# watch.net
KiCad netlist of a schematic drawn in EAGLE
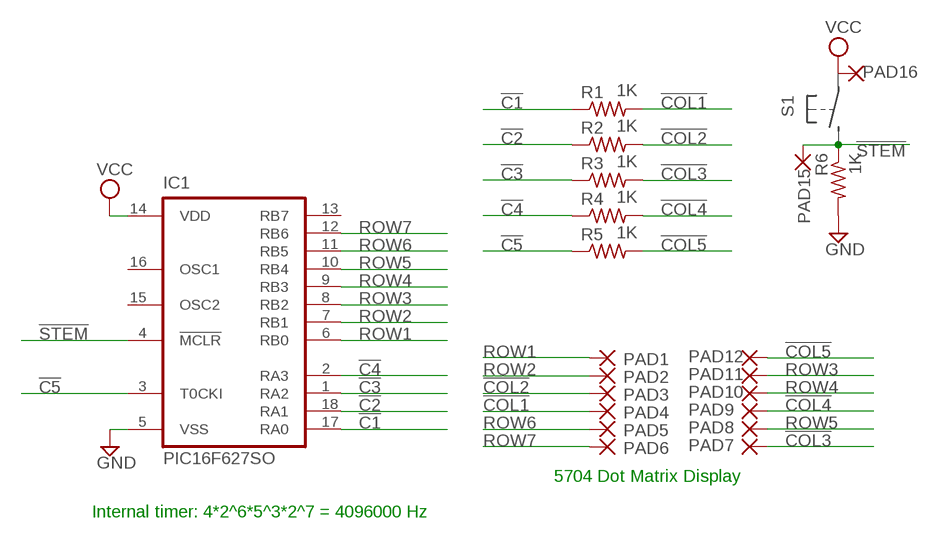
[diagram p0: schematic, sheet 1]

(export (version "E")
  (design (tool "Eeschema 10.0.6"))
  (components
    (comp (ref "IC1")
      (value "PIC16F627SO")
      (footprint "eagle-import:SO-18W")
      (fields (field (name "MF") "MICROCHIP") (field (name "MPN") "PIC16C622A-04I/SO"))
      (libsource (lib "eagle-import") (part "PIC16CSO622"))
    )
    (comp (ref "PAD1")
      (value "SMD2")
      (footprint "eagle-import:SMD1,27-2,54")
      (libsource (lib "eagle-import") (part "SMD2"))
    )
    (comp (ref "PAD2")
      (value "SMD2")
      (footprint "eagle-import:SMD1,27-2,54")
      (libsource (lib "eagle-import") (part "SMD2"))
    )
    (comp (ref "PAD3")
      (value "SMD2")
      (footprint "eagle-import:SMD1,27-2,54")
      (libsource (lib "eagle-import") (part "SMD2"))
    )
    (comp (ref "PAD4")
      (value "SMD2")
      (footprint "eagle-import:SMD1,27-2,54")
      (libsource (lib "eagle-import") (part "SMD2"))
    )
    (comp (ref "PAD5")
      (value "SMD2")
      (footprint "eagle-import:SMD1,27-2,54")
      (libsource (lib "eagle-import") (part "SMD2"))
    )
    (comp (ref "PAD6")
      (value "SMD2")
      (footprint "eagle-import:SMD1,27-2,54")
      (libsource (lib "eagle-import") (part "SMD2"))
    )
    (comp (ref "PAD7")
      (value "SMD2")
      (footprint "eagle-import:SMD1,27-2,54")
      (libsource (lib "eagle-import") (part "SMD2"))
    )
    (comp (ref "PAD8")
      (value "SMD2")
      (footprint "eagle-import:SMD1,27-2,54")
      (libsource (lib "eagle-import") (part "SMD2"))
    )
    (comp (ref "PAD9")
      (value "SMD2")
      (footprint "eagle-import:SMD1,27-2,54")
      (libsource (lib "eagle-import") (part "SMD2"))
    )
    (comp (ref "PAD10")
      (value "SMD2")
      (footprint "eagle-import:SMD1,27-2,54")
      (libsource (lib "eagle-import") (part "SMD2"))
    )
    (comp (ref "PAD11")
      (value "SMD2")
      (footprint "eagle-import:SMD1,27-2,54")
      (libsource (lib "eagle-import") (part "SMD2"))
    )
    (comp (ref "PAD12")
      (value "SMD2")
      (footprint "eagle-import:SMD1,27-2,54")
      (libsource (lib "eagle-import") (part "SMD2"))
    )
    (comp (ref "PAD15")
      (value "SMD2")
      (footprint "eagle-import:SMD1,27-2,54")
      (libsource (lib "eagle-import") (part "SMD2"))
    )
    (comp (ref "PAD16")
      (value "SMD2")
      (footprint "eagle-import:SMD1,27-2,54")
      (libsource (lib "eagle-import") (part "SMD2"))
    )
    (comp (ref "R1")
      (value "1K")
      (footprint "eagle-import:R0805")
      (libsource (lib "eagle-import") (part "R-US_R0805"))
    )
    (comp (ref "R2")
      (value "1K")
      (footprint "eagle-import:R0805")
      (libsource (lib "eagle-import") (part "R-US_R0805"))
    )
    (comp (ref "R3")
      (value "1K")
      (footprint "eagle-import:R0805")
      (libsource (lib "eagle-import") (part "R-US_R0805"))
    )
    (comp (ref "R4")
      (value "1K")
      (footprint "eagle-import:R0805")
      (libsource (lib "eagle-import") (part "R-US_R0805"))
    )
    (comp (ref "R5")
      (value "1K")
      (footprint "eagle-import:R0805")
      (libsource (lib "eagle-import") (part "R-US_R0805"))
    )
    (comp (ref "R6")
      (value "1K")
      (footprint "eagle-import:R0805")
      (libsource (lib "eagle-import") (part "R-US_R0805"))
    )
  )
  (nets
    (net (code "1") (name "/ROW1") (class "Default")
      (node (ref "IC1") (pin "6") (pinfunction "RB0_6") (pintype "bidirectional"))
      (node (ref "PAD1") (pin "1") (pinfunction "P_1") (pintype "passive"))
    )
    (net (code "2") (name "/ROW2") (class "Default")
      (node (ref "IC1") (pin "7") (pinfunction "RB1_7") (pintype "bidirectional"))
      (node (ref "PAD2") (pin "1") (pinfunction "P_1") (pintype "passive"))
    )
    (net (code "3") (name "/ROW3") (class "Default")
      (node (ref "IC1") (pin "8") (pinfunction "RB2_8") (pintype "bidirectional"))
      (node (ref "PAD11") (pin "1") (pinfunction "P_1") (pintype "passive"))
    )
    (net (code "4") (name "/ROW4") (class "Default")
      (node (ref "IC1") (pin "9") (pinfunction "RB3_9") (pintype "bidirectional"))
      (node (ref "PAD10") (pin "1") (pinfunction "P_1") (pintype "passive"))
    )
    (net (code "5") (name "/ROW5") (class "Default")
      (node (ref "IC1") (pin "10") (pinfunction "RB4_10") (pintype "bidirectional"))
      (node (ref "PAD8") (pin "1") (pinfunction "P_1") (pintype "passive"))
    )
    (net (code "6") (name "/ROW6") (class "Default")
      (node (ref "IC1") (pin "11") (pinfunction "RB5_11") (pintype "bidirectional"))
      (node (ref "PAD5") (pin "1") (pinfunction "P_1") (pintype "passive"))
    )
    (net (code "7") (name "/ROW7") (class "Default")
      (node (ref "IC1") (pin "12") (pinfunction "RB6_12") (pintype "bidirectional"))
      (node (ref "PAD6") (pin "1") (pinfunction "P_1") (pintype "passive"))
    )
    (net (code "8") (name "/~{C1}") (class "Default")
      (node (ref "IC1") (pin "17") (pinfunction "RA0_17") (pintype "bidirectional"))
      (node (ref "R1") (pin "1") (pinfunction "1_1") (pintype "passive"))
    )
    (net (code "9") (name "/~{C2}") (class "Default")
      (node (ref "IC1") (pin "18") (pinfunction "RA1_18") (pintype "bidirectional"))
      (node (ref "R2") (pin "1") (pinfunction "1_1") (pintype "passive"))
    )
    (net (code "10") (name "/~{C3}") (class "Default")
      (node (ref "IC1") (pin "1") (pinfunction "RA2_1") (pintype "bidirectional"))
      (node (ref "R3") (pin "1") (pinfunction "1_1") (pintype "passive"))
    )
    (net (code "11") (name "/~{C4}") (class "Default")
      (node (ref "IC1") (pin "2") (pinfunction "RA3_2") (pintype "bidirectional"))
      (node (ref "R4") (pin "1") (pinfunction "1_1") (pintype "passive"))
    )
    (net (code "12") (name "/~{C5}") (class "Default")
      (node (ref "IC1") (pin "3") (pinfunction "T0CKI_3") (pintype "input"))
      (node (ref "R5") (pin "1") (pinfunction "1_1") (pintype "passive"))
    )
    (net (code "13") (name "/~{COL1}") (class "Default")
      (node (ref "PAD4") (pin "1") (pinfunction "P_1") (pintype "passive"))
      (node (ref "R1") (pin "2") (pinfunction "2_2") (pintype "passive"))
    )
    (net (code "14") (name "/~{COL2}") (class "Default")
      (node (ref "PAD3") (pin "1") (pinfunction "P_1") (pintype "passive"))
      (node (ref "R2") (pin "2") (pinfunction "2_2") (pintype "passive"))
    )
    (net (code "15") (name "/~{COL3}") (class "Default")
      (node (ref "PAD7") (pin "1") (pinfunction "P_1") (pintype "passive"))
      (node (ref "R3") (pin "2") (pinfunction "2_2") (pintype "passive"))
    )
    (net (code "16") (name "/~{COL4}") (class "Default")
      (node (ref "PAD9") (pin "1") (pinfunction "P_1") (pintype "passive"))
      (node (ref "R4") (pin "2") (pinfunction "2_2") (pintype "passive"))
    )
    (net (code "17") (name "/~{COL5}") (class "Default")
      (node (ref "PAD12") (pin "1") (pinfunction "P_1") (pintype "passive"))
      (node (ref "R5") (pin "2") (pinfunction "2_2") (pintype "passive"))
    )
    (net (code "18") (name "/~{STEM}") (class "Default")
      (node (ref "IC1") (pin "4") (pinfunction "~{MCLR}_4") (pintype "input"))
      (node (ref "PAD15") (pin "1") (pinfunction "P_1") (pintype "passive"))
      (node (ref "R6") (pin "1") (pinfunction "1_1") (pintype "passive"))
    )
    (net (code "19") (name "GND") (class "Default")
      (node (ref "IC1") (pin "5") (pinfunction "VSS_5") (pintype "power_in"))
      (node (ref "R6") (pin "2") (pinfunction "2_2") (pintype "passive"))
    )
    (net (code "20") (name "VCC") (class "Default")
      (node (ref "IC1") (pin "14") (pinfunction "VDD_14") (pintype "power_in"))
      (node (ref "PAD16") (pin "1") (pinfunction "P_1") (pintype "passive"))
    )
    (net (code "21") (name "unconnected-(IC1-OSC1-Pad16)") (class "Default")
      (node (ref "IC1") (pin "16") (pinfunction "OSC1_16") (pintype "input"))
    )
    (net (code "22") (name "unconnected-(IC1-OSC2-Pad15)") (class "Default")
      (node (ref "IC1") (pin "15") (pinfunction "OSC2_15") (pintype "output"))
    )
    (net (code "23") (name "unconnected-(IC1-RB7-Pad13)") (class "Default")
      (node (ref "IC1") (pin "13") (pinfunction "RB7_13") (pintype "bidirectional"))
    )
  )
)
